# RelayDriver.net
KiCad netlist of a schematic drawn in Altium Designer
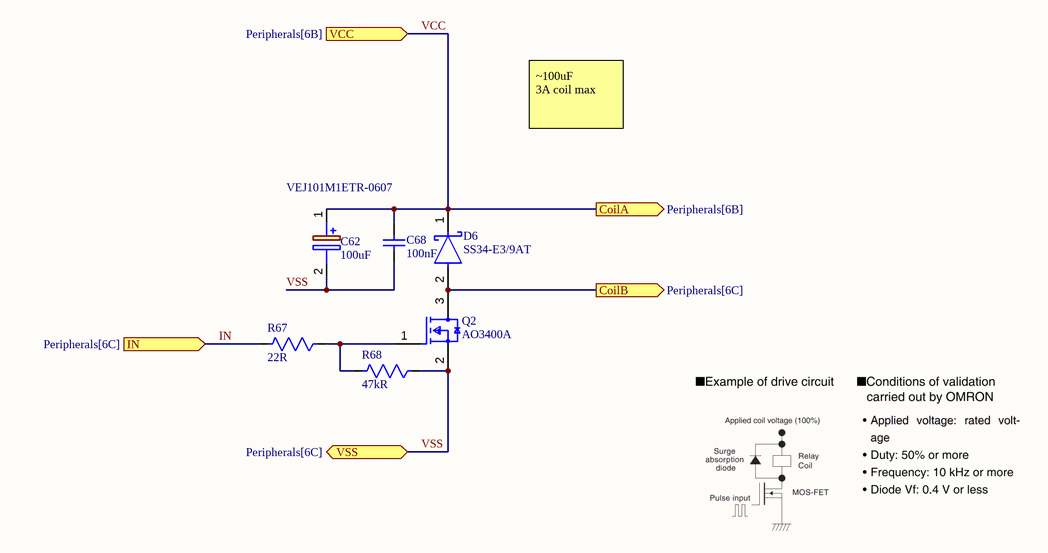
[diagram p0: RelayDriver.SchDoc]

(export (version "E")
  (design (tool "Eeschema 10.0.6"))
  (components
    (comp (ref "C62")
      (value "VEJ101M1ETR-0607")
      (footprint "FlexBMS_lib:CAPAE660X800N")
      (description "Capacitor Polarised")
      (fields (field (name "ALTIUM_VALUE") "100uF") (field (name "JLCPCB PART #") "C176664"))
      (libsource (lib "FlexBMS_lib") (part "VEJ101M1ETR-0607"))
    )
    (comp (ref "C68")
      (value "100nF")
      (footprint "WCAP-CSGP_0402_L1W0.5H0.5")
      (description "GTT Standard 0402 non-polarized capacitor")
      (fields (field (name "JLCPCB PART #") "C1525") (field (name "Comment") "CAP 0402 100nF X7R"))
      (libsource (lib "Green Team Twente") (part "CAP_NONPOL_GENERIC"))
    )
    (comp (ref "D6")
      (value "SS34-E3/9AT")
      (footprint "FP-SMC-MFG")
      (description "DIODE SCHOTTKY 40V 3A DO214AB")
      (fields (field (name "JLCPCB PART #") "C3008890"))
      (libsource (lib "Altium Content Vault") (part "c1678fac7984e62e0809fbf79c06691"))
    )
    (comp (ref "Q2")
      (value "AO3400A")
      (footprint "FP-SOT23-MFG")
      (description "MOSFET N-CH 30V 5.7A SOT23")
      (libsource (lib "Altium Content Vault") (part "0a9ea7c96deaaede766a5b531c28de0"))
    )
    (comp (ref "R67")
      (value "22R")
      (footprint "RES_SM0603_YAGEORC_N")
      (description "GTT Standard 0603 Resistor")
      (fields (field (name "POWER") "62.5mW") (field (name "TOLERANCE") "1%"))
      (libsource (lib "Green Team Twente") (part "RES_GENERIC"))
    )
    (comp (ref "R68")
      (value "47kR")
      (footprint "RES_SM0603_YAGEORC_N")
      (description "GTT Standard 0603 Resistor")
      (fields (field (name "POWER") "62.5mW") (field (name "TOLERANCE") "1%"))
      (libsource (lib "Green Team Twente") (part "RES_GENERIC"))
    )
  )
  (nets
    (net (code "1") (name "/CoilB") (class "Default")
      (node (ref "D6") (pin "2") (pinfunction "A_2") (pintype "passive"))
      (node (ref "Q2") (pin "3") (pinfunction "D_3") (pintype "passive"))
    )
    (net (code "2") (name "/IN") (class "Default")
      (node (ref "R67") (pin "2") (pinfunction "2_2") (pintype "passive"))
    )
    (net (code "3") (name "/VCC") (class "Default")
      (node (ref "C62") (pin "1") (pinfunction "+_1") (pintype "passive"))
      (node (ref "C68") (pin "2") (pinfunction "2_2") (pintype "passive"))
      (node (ref "D6") (pin "1") (pinfunction "C_1") (pintype "passive"))
    )
    (net (code "4") (name "/VSS") (class "Default")
      (node (ref "C62") (pin "2") (pinfunction "-_2") (pintype "passive"))
      (node (ref "C68") (pin "1") (pinfunction "1_1") (pintype "passive"))
      (node (ref "Q2") (pin "2") (pinfunction "S_2") (pintype "passive"))
      (node (ref "R68") (pin "1") (pinfunction "1_1") (pintype "passive"))
    )
    (net (code "5") (name "Net-(Q2-G)") (class "Default")
      (node (ref "Q2") (pin "1") (pinfunction "G_1") (pintype "passive"))
      (node (ref "R67") (pin "1") (pinfunction "1_1") (pintype "passive"))
      (node (ref "R68") (pin "2") (pinfunction "2_2") (pintype "passive"))
    )
  )
)
